# Main.net
KiCad netlist of a schematic drawn in Altium Designer
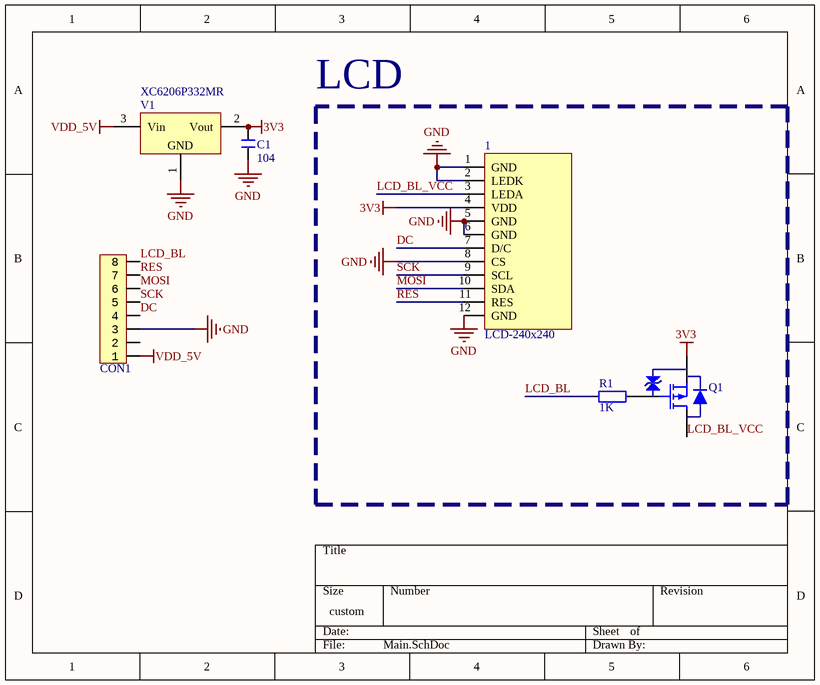
[diagram p0: Main.SchDoc]

(export (version "E")
  (design (tool "Eeschema 10.0.6"))
  (components
    (comp (ref "1")
      (value "LCD-240x240")
      (footprint "LCD-240x240-NoHole")
      (description "显示屏")
      (libsource (lib "mLib") (part "LCD-240x240"))
    )
    (comp (ref "C1")
      (value "104")
      (footprint "C 0402_M")
      (description "无极性贴片电容")
      (libsource (lib "ExtendBoard_1") (part "C"))
    )
    (comp (ref "CON1")
      (value "FFC_0.5_8")
      (footprint "FFC_0.5_8")
      (description "FFC")
      (libsource (lib "KitSprout") (part "FFC_0.5_8"))
    )
    (comp (ref "Q1")
      (value "AO3415A")
      (footprint "SOT23-3")
      (description "MOSFET")
      (fields (field (name "PUBLISHER") "Altium Limited"))
      (libsource (lib "MyPcbLib") (part "AO3415A"))
    )
    (comp (ref "R1")
      (value "1K")
      (footprint "RES_0402")
      (description "Resistor")
      (libsource (lib "MyPcbLib") (part "电阻-0402"))
    )
    (comp (ref "V1")
      (value "XC6206P332MR")
      (footprint "SOT23-3L")
      (description "低压差线性稳压芯片")
      (libsource (lib "ExtendBoard_1") (part "XC6206P332MR"))
    )
  )
  (nets
    (net (code "1") (name "/DC") (class "Default")
      (node (ref "1") (pin "7") (pinfunction "D/C_7") (pintype "passive"))
      (node (ref "CON1") (pin "4") (pinfunction "4_4") (pintype "passive"))
    )
    (net (code "2") (name "/LCD_BL") (class "Default")
      (node (ref "CON1") (pin "8") (pinfunction "8_8") (pintype "passive"))
      (node (ref "R1") (pin "1") (pinfunction "1_1") (pintype "passive"))
    )
    (net (code "3") (name "/LCD_BL_VCC") (class "Default")
      (node (ref "1") (pin "3") (pinfunction "LEDA_3") (pintype "passive"))
      (node (ref "Q1") (pin "3") (pinfunction "D_3") (pintype "passive"))
    )
    (net (code "4") (name "/MOSI") (class "Default")
      (node (ref "1") (pin "10") (pinfunction "SDA_10") (pintype "passive"))
      (node (ref "CON1") (pin "6") (pinfunction "6_6") (pintype "passive"))
    )
    (net (code "5") (name "/RES") (class "Default")
      (node (ref "1") (pin "11") (pinfunction "RES_11") (pintype "passive"))
      (node (ref "CON1") (pin "7") (pinfunction "7_7") (pintype "passive"))
    )
    (net (code "6") (name "/SCK") (class "Default")
      (node (ref "1") (pin "9") (pinfunction "SCL_9") (pintype "passive"))
      (node (ref "CON1") (pin "5") (pinfunction "5_5") (pintype "passive"))
    )
    (net (code "7") (name "3V3") (class "Default")
      (node (ref "1") (pin "4") (pinfunction "VDD_4") (pintype "passive"))
      (node (ref "C1") (pin "2") (pinfunction "2_2") (pintype "passive"))
      (node (ref "Q1") (pin "2") (pinfunction "S_2") (pintype "passive"))
      (node (ref "V1") (pin "2") (pinfunction "Vout_2") (pintype "passive"))
    )
    (net (code "8") (name "GND") (class "Default")
      (node (ref "1") (pin "1") (pinfunction "GND_1") (pintype "passive"))
      (node (ref "1") (pin "12") (pinfunction "GND_12") (pintype "passive"))
      (node (ref "1") (pin "2") (pinfunction "LEDK_2") (pintype "passive"))
      (node (ref "1") (pin "5") (pinfunction "GND_5") (pintype "passive"))
      (node (ref "1") (pin "6") (pinfunction "GND_6") (pintype "passive"))
      (node (ref "1") (pin "8") (pinfunction "CS_8") (pintype "passive"))
      (node (ref "C1") (pin "1") (pinfunction "1_1") (pintype "passive"))
      (node (ref "CON1") (pin "3") (pinfunction "3_3") (pintype "passive"))
      (node (ref "V1") (pin "1") (pinfunction "GND_1") (pintype "passive"))
    )
    (net (code "9") (name "Net-(Q1-G)") (class "Default")
      (node (ref "Q1") (pin "1") (pinfunction "G_1") (pintype "passive"))
      (node (ref "R1") (pin "2") (pinfunction "2_2") (pintype "passive"))
    )
    (net (code "10") (name "VDD_5V") (class "Default")
      (node (ref "CON1") (pin "1") (pinfunction "1_1") (pintype "passive"))
      (node (ref "V1") (pin "3") (pinfunction "Vin_3") (pintype "passive"))
    )
    (net (code "11") (name "unconnected-(CON1-Pad2)") (class "Default")
      (node (ref "CON1") (pin "2") (pinfunction "2_2") (pintype "passive"))
    )
  )
)
